# MB_Nano_V6s.net
KiCad netlist of a schematic drawn in EAGLE
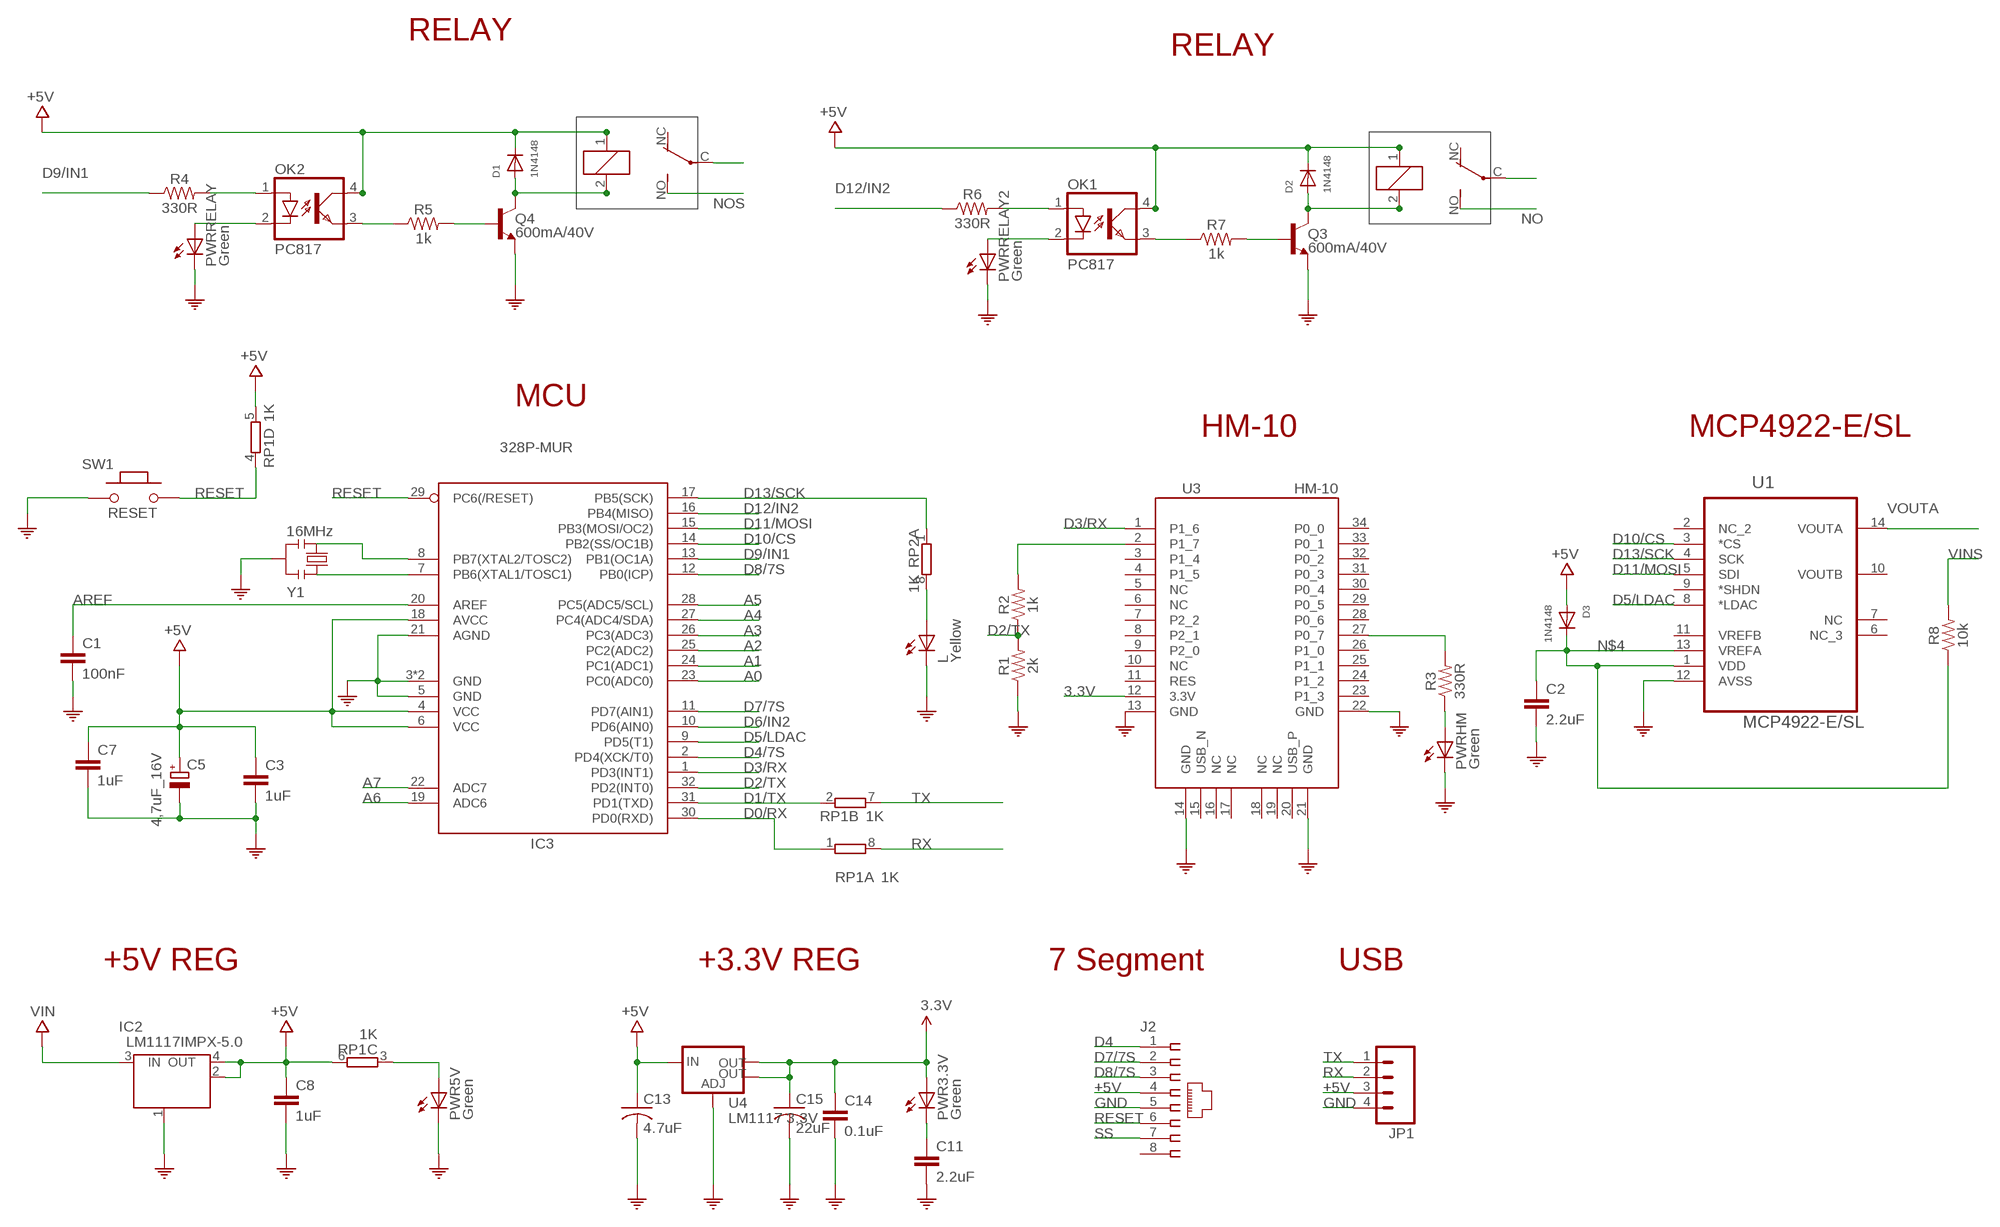
[diagram p0: schematic, sheet 1]

(export (version "E")
  (design (tool "Eeschema 10.0.6"))
  (components
    (comp (ref "C1")
      (value "100nF")
      (footprint "eagle-import:C0603-ROUND")
      (fields (field (name "PART_NUMBER") "cl10b104kbnc"))
      (libsource (lib "eagle-import") (part "0015_100NF_0603"))
    )
    (comp (ref "C2")
      (value "2.2uF")
      (footprint "eagle-import:C0603-ROUND")
      (fields (field (name "PART_NUMBER") "1uF_0603/GRM188R61E105KA12D"))
      (libsource (lib "eagle-import") (part "0006_1UF_0603/GRM188R61E105KA12D"))
    )
    (comp (ref "C3")
      (value "1uF")
      (footprint "eagle-import:C0603-ROUND")
      (fields (field (name "PART_NUMBER") "1uF_0603/GRM188R61E105KA12D"))
      (libsource (lib "eagle-import") (part "0006_1UF_0603/GRM188R61E105KA12D"))
    )
    (comp (ref "C5")
      (value "4,7uF_16V")
      (footprint "eagle-import:TAN-A")
      (fields (field (name "PART_NUMBER") "TAJA475MO16RNJ"))
      (libsource (lib "eagle-import") (part "0833_TAJA475MO16RNJ"))
    )
    (comp (ref "C7")
      (value "1uF")
      (footprint "eagle-import:C0603-ROUND")
      (fields (field (name "PART_NUMBER") "1uF_0603/GRM188R61E105KA12D"))
      (libsource (lib "eagle-import") (part "0006_1UF_0603/GRM188R61E105KA12D"))
    )
    (comp (ref "C8")
      (value "1uF")
      (footprint "eagle-import:C0603-ROUND")
      (fields (field (name "PART_NUMBER") "1uF_0603/GRM188R61E105KA12D"))
      (libsource (lib "eagle-import") (part "0006_1UF_0603/GRM188R61E105KA12D"))
    )
    (comp (ref "C11")
      (value "2.2uF")
      (footprint "eagle-import:C0603-ROUND")
      (fields (field (name "PART_NUMBER") "1uF_0603/GRM188R61E105KA12D"))
      (libsource (lib "eagle-import") (part "0006_1UF_0603/GRM188R61E105KA12D"))
    )
    (comp (ref "C13")
      (value "4.7uF")
      (footprint "eagle-import:C1206")
      (libsource (lib "eagle-import") (part "C-USC1206"))
    )
    (comp (ref "C14")
      (value "0.1uF")
      (footprint "eagle-import:0805")
      (libsource (lib "eagle-import") (part "CAP0805"))
    )
    (comp (ref "C15")
      (value "22uF")
      (footprint "eagle-import:C1206")
      (libsource (lib "eagle-import") (part "C-USC1206"))
    )
    (comp (ref "D1")
      (value "1N4148")
      (footprint "eagle-import:SOD-523")
      (libsource (lib "eagle-import") (part "DIODESOD-523"))
    )
    (comp (ref "D2")
      (value "1N4148")
      (footprint "eagle-import:SOD-523")
      (libsource (lib "eagle-import") (part "DIODESOD-523"))
    )
    (comp (ref "D3")
      (value "1N4148")
      (footprint "eagle-import:SOD-523")
      (libsource (lib "eagle-import") (part "DIODESOD-523"))
    )
    (comp (ref "IC2")
      (value "LM1117IMPX-5.0")
      (footprint "eagle-import:LINEAR_SOT223")
      (libsource (lib "eagle-import") (part "0022_LM1117IMPX-5.0"))
    )
    (comp (ref "IC3")
      (value "328P-MUR")
      (footprint "eagle-import:VQFN32")
      (fields (field (name "MANUFACTURER") "ATMEL"))
      (libsource (lib "eagle-import") (part "ATMEGA328P-32MUR"))
    )
    (comp (ref "J2")
      (value "520259-4")
      (footprint "eagle-import:520259-4")
      (libsource (lib "eagle-import") (part "520259-4"))
    )
    (comp (ref "JP1")
      (value "M04POLAR_LOCK")
      (footprint "eagle-import:MOLEX-1X4_LOCK")
      (libsource (lib "eagle-import") (part "M04POLAR_LOCK"))
    )
    (comp (ref "L")
      (value "Yellow")
      (footprint "eagle-import:CHIPLED_0805")
      (fields (field (name "PART_NUMBER") "KPT-2012YC"))
      (libsource (lib "eagle-import") (part "0044_KPT-2012YC"))
    )
    (comp (ref "OK1")
      (value "PC817")
      (footprint "eagle-import:DIL04")
      (fields (field (name "MPN") "PC817X4J000F"))
      (libsource (lib "eagle-import") (part "PC817"))
    )
    (comp (ref "OK2")
      (value "PC817")
      (footprint "eagle-import:DIL04")
      (fields (field (name "MPN") "PC817X4J000F"))
      (libsource (lib "eagle-import") (part "PC817"))
    )
    (comp (ref "PWR3.3V")
      (value "Green")
      (footprint "eagle-import:CHIPLED_0805")
      (fields (field (name "PART_NUMBER") "KPT-2012SGC"))
      (libsource (lib "eagle-import") (part "0043_KPT-2012SGC"))
    )
    (comp (ref "PWR5V")
      (value "Green")
      (footprint "eagle-import:CHIPLED_0805")
      (fields (field (name "PART_NUMBER") "KPT-2012SGC"))
      (libsource (lib "eagle-import") (part "0043_KPT-2012SGC"))
    )
    (comp (ref "PWRHM")
      (value "Green")
      (footprint "eagle-import:CHIPLED_0805")
      (fields (field (name "PART_NUMBER") "KPT-2012SGC"))
      (libsource (lib "eagle-import") (part "0043_KPT-2012SGC"))
    )
    (comp (ref "PWRRELAY")
      (value "Green")
      (footprint "eagle-import:CHIPLED_0805")
      (fields (field (name "PART_NUMBER") "KPT-2012SGC"))
      (libsource (lib "eagle-import") (part "0043_KPT-2012SGC"))
    )
    (comp (ref "PWRRELAY2")
      (value "Green")
      (footprint "eagle-import:CHIPLED_0805")
      (fields (field (name "PART_NUMBER") "KPT-2012SGC"))
      (libsource (lib "eagle-import") (part "0043_KPT-2012SGC"))
    )
    (comp (ref "Q3")
      (value "600mA/40V")
      (footprint "eagle-import:SOT23-3")
      (libsource (lib "eagle-import") (part "TRANS_NPN-MMBT2222AL"))
    )
    (comp (ref "Q4")
      (value "600mA/40V")
      (footprint "eagle-import:SOT23-3")
      (libsource (lib "eagle-import") (part "TRANS_NPN-MMBT2222AL"))
    )
    (comp (ref "R1")
      (value "2k")
      (footprint "eagle-import:0603")
      (libsource (lib "eagle-import") (part "33OHM-0603-1/10W-1%"))
    )
    (comp (ref "R2")
      (value "1k")
      (footprint "eagle-import:0603")
      (libsource (lib "eagle-import") (part "33OHM-0603-1/10W-1%"))
    )
    (comp (ref "R3")
      (value "330R")
      (footprint "eagle-import:0603")
      (libsource (lib "eagle-import") (part "33OHM-0603-1/10W-1%"))
    )
    (comp (ref "R4")
      (value "330R")
      (footprint "eagle-import:0603")
      (libsource (lib "eagle-import") (part "33OHM-0603-1/10W-1%"))
    )
    (comp (ref "R5")
      (value "1k")
      (footprint "eagle-import:0603")
      (libsource (lib "eagle-import") (part "1KOHM-0603-1/10W-1%"))
    )
    (comp (ref "R6")
      (value "330R")
      (footprint "eagle-import:0603")
      (libsource (lib "eagle-import") (part "33OHM-0603-1/10W-1%"))
    )
    (comp (ref "R7")
      (value "1k")
      (footprint "eagle-import:0603")
      (libsource (lib "eagle-import") (part "1KOHM-0603-1/10W-1%"))
    )
    (comp (ref "R8")
      (value "10k")
      (footprint "eagle-import:0603")
      (libsource (lib "eagle-import") (part "1KOHM-0603-1/10W-1%"))
    )
    (comp (ref "RELAY5VDC")
      (value "RELAY 5VDC")
      (footprint "eagle-import:CQ1")
      (libsource (lib "eagle-import") (part "CQ1-12V"))
    )
    (comp (ref "RELAY5VDC1")
      (value "RELAY 5VDC")
      (footprint "eagle-import:CQ1")
      (libsource (lib "eagle-import") (part "CQ1-12V"))
    )
    (comp (ref "RP1")
      (value "1K")
      (footprint "eagle-import:CAY16")
      (fields (field (name "PART_NUMBER") "064R_1K_/_CAY16-102J4LF"))
      (libsource (lib "eagle-import") (part "0005_064R_1K_/_CAY16-102J4LF"))
    )
    (comp (ref "RP2")
      (value "1K")
      (footprint "eagle-import:CAY16")
      (fields (field (name "PART_NUMBER") "064R_1K_/_CAY16-102J4LF"))
      (libsource (lib "eagle-import") (part "0005_064R_1K_/_CAY16-102J4LF"))
    )
    (comp (ref "SW1")
      (value "RESET")
      (footprint "eagle-import:SMD_157SW")
      (fields (field (name "PART_NUMBER") "IT-1185AP1C-160G-G_T&R"))
      (libsource (lib "eagle-import") (part "0173_IT-1185AP1C-160G-G_T&R"))
    )
    (comp (ref "U1")
      (value "MCP4922-E/SL")
      (footprint "eagle-import:SOIC127P600X175-14N")
      (libsource (lib "eagle-import") (part "MCP4922-E/SL"))
    )
    (comp (ref "U3")
      (value "HM-10")
      (footprint "eagle-import:HM-10")
      (libsource (lib "eagle-import") (part "HM-10"))
    )
    (comp (ref "U4")
      (value "LM1117 3.3V")
      (footprint "eagle-import:SOT223")
      (libsource (lib "eagle-import") (part "V_REG_LM1117SOT223"))
    )
    (comp (ref "Y1")
      (value "16MHz")
      (footprint "eagle-import:RESONATOR")
      (fields (field (name "PART_NUMBER") "CSTCE16M0V53-R0"))
      (libsource (lib "eagle-import") (part "0011_CSTCE16M0V53-R0"))
    )
  )
  (nets
    (net (code "1") (name "+5V") (class "Default")
      (node (ref "C13") (pin "1") (pinfunction "1_1") (pintype "passive"))
      (node (ref "C3") (pin "1") (pinfunction "1_1") (pintype "passive"))
      (node (ref "C5") (pin "1") (pinfunction "+_1") (pintype "passive"))
      (node (ref "C7") (pin "1") (pinfunction "1_1") (pintype "passive"))
      (node (ref "C8") (pin "1") (pinfunction "1_1") (pintype "passive"))
      (node (ref "D1") (pin "K") (pinfunction "C_K") (pintype "passive"))
      (node (ref "D2") (pin "K") (pinfunction "C_K") (pintype "passive"))
      (node (ref "D3") (pin "A") (pinfunction "A_A") (pintype "passive"))
      (node (ref "IC2") (pin "2") (pinfunction "OUT_2") (pintype "passive"))
      (node (ref "IC2") (pin "4") (pinfunction "OUT_4") (pintype "passive"))
      (node (ref "IC3") (pin "18") (pinfunction "AVCC_18") (pintype "bidirectional"))
      (node (ref "IC3") (pin "4") (pinfunction "VCC_4") (pintype "bidirectional"))
      (node (ref "IC3") (pin "6") (pinfunction "VCC_6") (pintype "bidirectional"))
      (node (ref "J2") (pin "4") (pinfunction "4_4") (pintype "passive"))
      (node (ref "JP1") (pin "3") (pinfunction "3_3") (pintype "passive"))
      (node (ref "OK1") (pin "4") (pinfunction "COL_4") (pintype "passive"))
      (node (ref "OK2") (pin "4") (pinfunction "COL_4") (pintype "passive"))
      (node (ref "RELAY5VDC") (pin "1") (pinfunction "1_1") (pintype "passive"))
      (node (ref "RELAY5VDC1") (pin "1") (pinfunction "1_1") (pintype "passive"))
      (node (ref "RP1") (pin "5") (pinfunction "2_5") (pintype "passive"))
      (node (ref "RP1") (pin "6") (pinfunction "2_6") (pintype "passive"))
      (node (ref "U4") (pin "3") (pinfunction "IN_3") (pintype "input"))
    )
    (net (code "2") (name "/A0") (class "Default")
      (node (ref "IC3") (pin "23") (pinfunction "PC0(ADC0)_23") (pintype "bidirectional"))
    )
    (net (code "3") (name "/A1") (class "Default")
      (node (ref "IC3") (pin "24") (pinfunction "PC1(ADC1)_24") (pintype "bidirectional"))
    )
    (net (code "4") (name "/A2") (class "Default")
      (node (ref "IC3") (pin "25") (pinfunction "PC2(ADC2)_25") (pintype "bidirectional"))
    )
    (net (code "5") (name "/A3") (class "Default")
      (node (ref "IC3") (pin "26") (pinfunction "PC3(ADC3)_26") (pintype "bidirectional"))
    )
    (net (code "6") (name "/A4") (class "Default")
      (node (ref "IC3") (pin "27") (pinfunction "PC4(ADC4/SDA)_27") (pintype "bidirectional"))
    )
    (net (code "7") (name "/A5") (class "Default")
      (node (ref "IC3") (pin "28") (pinfunction "PC5(ADC5/SCL)_28") (pintype "bidirectional"))
    )
    (net (code "8") (name "/A6") (class "Default")
      (node (ref "IC3") (pin "19") (pinfunction "ADC6_19") (pintype "bidirectional"))
    )
    (net (code "9") (name "/A7") (class "Default")
      (node (ref "IC3") (pin "22") (pinfunction "ADC7_22") (pintype "bidirectional"))
    )
    (net (code "10") (name "/AREF") (class "Default")
      (node (ref "C1") (pin "1") (pinfunction "1_1") (pintype "passive"))
      (node (ref "IC3") (pin "20") (pinfunction "AREF_20") (pintype "bidirectional"))
    )
    (net (code "11") (name "/D0{slash}RX") (class "Default")
      (node (ref "IC3") (pin "30") (pinfunction "PD0(RXD)_30") (pintype "bidirectional"))
      (node (ref "RP1") (pin "1") (pinfunction "1_1") (pintype "passive"))
    )
    (net (code "12") (name "/D1{slash}TX") (class "Default")
      (node (ref "IC3") (pin "31") (pinfunction "PD1(TXD)_31") (pintype "bidirectional"))
      (node (ref "RP1") (pin "2") (pinfunction "1_2") (pintype "passive"))
    )
    (net (code "13") (name "/D2{slash}TX") (class "Default")
      (node (ref "IC3") (pin "32") (pinfunction "PD2(INT0)_32") (pintype "bidirectional"))
      (node (ref "R1") (pin "2") (pinfunction "2_2") (pintype "passive"))
      (node (ref "R2") (pin "1") (pinfunction "1_1") (pintype "passive"))
    )
    (net (code "14") (name "/D3{slash}RX") (class "Default")
      (node (ref "IC3") (pin "1") (pinfunction "PD3(INT1)_1") (pintype "bidirectional"))
      (node (ref "U3") (pin "1") (pinfunction "P1_6_1") (pintype "bidirectional"))
    )
    (net (code "15") (name "/D4") (class "Default")
      (node (ref "J2") (pin "1") (pinfunction "1_1") (pintype "passive"))
    )
    (net (code "16") (name "/D4{slash}7S") (class "Default")
      (node (ref "IC3") (pin "2") (pinfunction "PD4(XCK/T0)_2") (pintype "bidirectional"))
    )
    (net (code "17") (name "/D5{slash}LDAC") (class "Default")
      (node (ref "IC3") (pin "9") (pinfunction "PD5(T1)_9") (pintype "bidirectional"))
      (node (ref "U1") (pin "8") (pinfunction "*LDAC_8") (pintype "input"))
    )
    (net (code "18") (name "/D6{slash}IN2") (class "Default")
      (node (ref "IC3") (pin "10") (pinfunction "PD6(AIN0)_10") (pintype "bidirectional"))
    )
    (net (code "19") (name "/D7{slash}7S") (class "Default")
      (node (ref "IC3") (pin "11") (pinfunction "PD7(AIN1)_11") (pintype "bidirectional"))
      (node (ref "J2") (pin "2") (pinfunction "2_2") (pintype "passive"))
    )
    (net (code "20") (name "/D8{slash}7S") (class "Default")
      (node (ref "IC3") (pin "12") (pinfunction "PB0(ICP)_12") (pintype "bidirectional"))
      (node (ref "J2") (pin "3") (pinfunction "3_3") (pintype "passive"))
    )
    (net (code "21") (name "/D9{slash}IN1") (class "Default")
      (node (ref "IC3") (pin "13") (pinfunction "PB1(OC1A)_13") (pintype "bidirectional"))
      (node (ref "R4") (pin "1") (pinfunction "1_1") (pintype "passive"))
    )
    (net (code "22") (name "/D10{slash}CS") (class "Default")
      (node (ref "IC3") (pin "14") (pinfunction "PB2(SS/OC1B)_14") (pintype "bidirectional"))
      (node (ref "U1") (pin "3") (pinfunction "*CS_3") (pintype "input"))
    )
    (net (code "23") (name "/D11{slash}MOSI") (class "Default")
      (node (ref "IC3") (pin "15") (pinfunction "PB3(MOSI/OC2)_15") (pintype "bidirectional"))
      (node (ref "U1") (pin "5") (pinfunction "SDI_5") (pintype "input"))
    )
    (net (code "24") (name "/D12{slash}IN2") (class "Default")
      (node (ref "IC3") (pin "16") (pinfunction "PB4(MISO)_16") (pintype "bidirectional"))
      (node (ref "R6") (pin "1") (pinfunction "1_1") (pintype "passive"))
    )
    (net (code "25") (name "/D13{slash}SCK") (class "Default")
      (node (ref "IC3") (pin "17") (pinfunction "PB5(SCK)_17") (pintype "bidirectional"))
      (node (ref "RP2") (pin "1") (pinfunction "1_1") (pintype "passive"))
      (node (ref "U1") (pin "4") (pinfunction "SCK_4") (pintype "input"))
    )
    (net (code "26") (name "/GND") (class "Default")
      (node (ref "J2") (pin "5") (pinfunction "5_5") (pintype "passive"))
      (node (ref "JP1") (pin "4") (pinfunction "4_4") (pintype "passive"))
    )
    (net (code "27") (name "/N$4") (class "Default")
      (node (ref "C11") (pin "1") (pinfunction "1_1") (pintype "passive"))
      (node (ref "C2") (pin "1") (pinfunction "1_1") (pintype "passive"))
      (node (ref "D3") (pin "K") (pinfunction "C_K") (pintype "passive"))
      (node (ref "PWR3.3V") (pin "C") (pinfunction "C_C") (pintype "passive"))
      (node (ref "R8") (pin "1") (pinfunction "1_1") (pintype "passive"))
      (node (ref "U1") (pin "1") (pinfunction "VDD_1") (pintype "power_in"))
      (node (ref "U1") (pin "13") (pinfunction "VREFA_13") (pintype "input"))
    )
    (net (code "28") (name "/NO") (class "Default")
      (node (ref "RELAY5VDC") (pin "NO") (pinfunction "S_NO") (pintype "passive"))
    )
    (net (code "29") (name "/NOS") (class "Default")
      (node (ref "RELAY5VDC1") (pin "NO") (pinfunction "S_NO") (pintype "passive"))
    )
    (net (code "30") (name "/RESET") (class "Default")
      (node (ref "IC3") (pin "29") (pinfunction "PC6(/RESET)_29") (pintype "bidirectional"))
      (node (ref "J2") (pin "6") (pinfunction "6_6") (pintype "passive"))
      (node (ref "RP1") (pin "4") (pinfunction "1_4") (pintype "passive"))
      (node (ref "SW1") (pin "2") (pinfunction "2_2") (pintype "passive"))
    )
    (net (code "31") (name "/RX") (class "Default")
      (node (ref "JP1") (pin "2") (pinfunction "2_2") (pintype "passive"))
      (node (ref "RP1") (pin "8") (pinfunction "2_8") (pintype "passive"))
    )
    (net (code "32") (name "/SS") (class "Default")
      (node (ref "J2") (pin "7") (pinfunction "7_7") (pintype "passive"))
    )
    (net (code "33") (name "/TX") (class "Default")
      (node (ref "JP1") (pin "1") (pinfunction "1_1") (pintype "passive"))
      (node (ref "RP1") (pin "7") (pinfunction "2_7") (pintype "passive"))
    )
    (net (code "34") (name "/VINS") (class "Default")
      (node (ref "R8") (pin "2") (pinfunction "2_2") (pintype "passive"))
    )
    (net (code "35") (name "/VOUTA") (class "Default")
      (node (ref "U1") (pin "14") (pinfunction "VOUTA_14") (pintype "output"))
    )
    (net (code "36") (name "3.3V") (class "Default")
      (node (ref "C14") (pin "1") (pinfunction "1_1") (pintype "passive"))
      (node (ref "C15") (pin "1") (pinfunction "1_1") (pintype "passive"))
      (node (ref "PWR3.3V") (pin "A") (pinfunction "A_A") (pintype "passive"))
      (node (ref "U3") (pin "12") (pinfunction "3.3V_12") (pintype "bidirectional"))
      (node (ref "U4") (pin "2") (pinfunction "OUT_2") (pintype "output"))
      (node (ref "U4") (pin "4") (pinfunction "OUT_4") (pintype "output"))
    )
    (net (code "37") (name "COM") (class "Default")
      (node (ref "C1") (pin "2") (pinfunction "2_2") (pintype "passive"))
      (node (ref "C11") (pin "2") (pinfunction "2_2") (pintype "passive"))
      (node (ref "C13") (pin "2") (pinfunction "2_2") (pintype "passive"))
      (node (ref "C14") (pin "2") (pinfunction "2_2") (pintype "passive"))
      (node (ref "C15") (pin "2") (pinfunction "2_2") (pintype "passive"))
      (node (ref "C2") (pin "2") (pinfunction "2_2") (pintype "passive"))
      (node (ref "C3") (pin "2") (pinfunction "2_2") (pintype "passive"))
      (node (ref "C5") (pin "2") (pinfunction "-_2") (pintype "passive"))
      (node (ref "C7") (pin "2") (pinfunction "2_2") (pintype "passive"))
      (node (ref "C8") (pin "2") (pinfunction "2_2") (pintype "passive"))
      (node (ref "IC2") (pin "1") (pinfunction "GND/ADJ_1") (pintype "input"))
      (node (ref "IC3") (pin "21") (pinfunction "AGND_21") (pintype "bidirectional"))
      (node (ref "IC3") (pin "3") (pinfunction "GND_3") (pintype "bidirectional"))
      (node (ref "IC3") (pin "33") (pinfunction "GND_33") (pintype "bidirectional"))
      (node (ref "IC3") (pin "5") (pinfunction "GND_5") (pintype "bidirectional"))
      (node (ref "L") (pin "C") (pinfunction "C_C") (pintype "passive"))
      (node (ref "PWR5V") (pin "C") (pinfunction "C_C") (pintype "passive"))
      (node (ref "PWRHM") (pin "C") (pinfunction "C_C") (pintype "passive"))
      (node (ref "PWRRELAY") (pin "C") (pinfunction "C_C") (pintype "passive"))
      (node (ref "PWRRELAY2") (pin "C") (pinfunction "C_C") (pintype "passive"))
      (node (ref "Q3") (pin "2") (pinfunction "E_2") (pintype "passive"))
      (node (ref "Q4") (pin "2") (pinfunction "E_2") (pintype "passive"))
      (node (ref "R1") (pin "1") (pinfunction "1_1") (pintype "passive"))
      (node (ref "SW1") (pin "1") (pinfunction "1_1") (pintype "passive"))
      (node (ref "U1") (pin "12") (pinfunction "AVSS_12") (pintype "passive"))
      (node (ref "U3") (pin "13") (pinfunction "GND_13") (pintype "bidirectional"))
      (node (ref "U3") (pin "14") (pinfunction "GND_14") (pintype "bidirectional"))
      (node (ref "U3") (pin "21") (pinfunction "GND_21") (pintype "bidirectional"))
      (node (ref "U3") (pin "22") (pinfunction "GND_22") (pintype "bidirectional"))
      (node (ref "U4") (pin "1") (pinfunction "ADJ_1") (pintype "input"))
      (node (ref "Y1") (pin "2") (pinfunction "2_2") (pintype "passive"))
    )
    (net (code "38") (name "Net-(IC3-PB6(XTAL1{slash}TOSC1))") (class "Default")
      (node (ref "IC3") (pin "7") (pinfunction "PB6(XTAL1/TOSC1)_7") (pintype "bidirectional"))
      (node (ref "Y1") (pin "1") (pinfunction "1_1") (pintype "passive"))
    )
    (net (code "39") (name "Net-(IC3-PB7(XTAL2{slash}TOSC2))") (class "Default")
      (node (ref "IC3") (pin "8") (pinfunction "PB7(XTAL2/TOSC2)_8") (pintype "bidirectional"))
      (node (ref "Y1") (pin "3") (pinfunction "3_3") (pintype "passive"))
    )
    (net (code "40") (name "Net-(OK1-A)") (class "Default")
      (node (ref "OK1") (pin "1") (pinfunction "A_1") (pintype "passive"))
      (node (ref "R6") (pin "2") (pinfunction "2_2") (pintype "passive"))
    )
    (net (code "41") (name "Net-(OK1-C)") (class "Default")
      (node (ref "OK1") (pin "2") (pinfunction "C_2") (pintype "passive"))
      (node (ref "PWRRELAY2") (pin "A") (pinfunction "A_A") (pintype "passive"))
    )
    (net (code "42") (name "Net-(OK1-EMIT)") (class "Default")
      (node (ref "OK1") (pin "3") (pinfunction "EMIT_3") (pintype "passive"))
      (node (ref "R7") (pin "1") (pinfunction "1_1") (pintype "passive"))
    )
    (net (code "43") (name "Net-(OK2-A)") (class "Default")
      (node (ref "OK2") (pin "1") (pinfunction "A_1") (pintype "passive"))
      (node (ref "R4") (pin "2") (pinfunction "2_2") (pintype "passive"))
    )
    (net (code "44") (name "Net-(OK2-C)") (class "Default")
      (node (ref "OK2") (pin "2") (pinfunction "C_2") (pintype "passive"))
      (node (ref "PWRRELAY") (pin "A") (pinfunction "A_A") (pintype "passive"))
    )
    (net (code "45") (name "Net-(OK2-EMIT)") (class "Default")
      (node (ref "OK2") (pin "3") (pinfunction "EMIT_3") (pintype "passive"))
      (node (ref "R5") (pin "1") (pinfunction "1_1") (pintype "passive"))
    )
    (net (code "46") (name "Net-(PWRHM-PadA)") (class "Default")
      (node (ref "PWRHM") (pin "A") (pinfunction "A_A") (pintype "passive"))
      (node (ref "R3") (pin "1") (pinfunction "1_1") (pintype "passive"))
    )
    (net (code "47") (name "Net-(Q3-B)") (class "Default")
      (node (ref "Q3") (pin "1") (pinfunction "B_1") (pintype "passive"))
      (node (ref "R7") (pin "2") (pinfunction "2_2") (pintype "passive"))
    )
    (net (code "48") (name "Net-(Q3-C)") (class "Default")
      (node (ref "D2") (pin "A") (pinfunction "A_A") (pintype "passive"))
      (node (ref "Q3") (pin "3") (pinfunction "C_3") (pintype "passive"))
      (node (ref "RELAY5VDC") (pin "2") (pinfunction "2_2") (pintype "passive"))
    )
    (net (code "49") (name "Net-(Q4-B)") (class "Default")
      (node (ref "Q4") (pin "1") (pinfunction "B_1") (pintype "passive"))
      (node (ref "R5") (pin "2") (pinfunction "2_2") (pintype "passive"))
    )
    (net (code "50") (name "Net-(Q4-C)") (class "Default")
      (node (ref "D1") (pin "A") (pinfunction "A_A") (pintype "passive"))
      (node (ref "Q4") (pin "3") (pinfunction "C_3") (pintype "passive"))
      (node (ref "RELAY5VDC1") (pin "2") (pinfunction "2_2") (pintype "passive"))
    )
    (net (code "51") (name "Net-(RP1C-1)") (class "Default")
      (node (ref "PWR5V") (pin "A") (pinfunction "A_A") (pintype "passive"))
      (node (ref "RP1") (pin "3") (pinfunction "1_3") (pintype "passive"))
    )
    (net (code "52") (name "Net-(RP2A-2)") (class "Default")
      (node (ref "L") (pin "A") (pinfunction "A_A") (pintype "passive"))
      (node (ref "RP2") (pin "8") (pinfunction "2_8") (pintype "passive"))
    )
    (net (code "53") (name "Net-(U3-P0_7)") (class "Default")
      (node (ref "R3") (pin "2") (pinfunction "2_2") (pintype "passive"))
      (node (ref "U3") (pin "27") (pinfunction "P0_7_27") (pintype "bidirectional"))
    )
    (net (code "54") (name "Net-(U3-P1_7)") (class "Default")
      (node (ref "R2") (pin "2") (pinfunction "2_2") (pintype "passive"))
      (node (ref "U3") (pin "2") (pinfunction "P1_7_2") (pintype "bidirectional"))
    )
    (net (code "55") (name "VIN") (class "Default")
      (node (ref "IC2") (pin "3") (pinfunction "IN_3") (pintype "input"))
    )
    (net (code "56") (name "unconnected-(J2-Pad8)") (class "Default")
      (node (ref "J2") (pin "8") (pinfunction "8_8") (pintype "passive"))
    )
    (net (code "57") (name "unconnected-(RELAY5VDC1B-O-PadNC)") (class "Default")
      (node (ref "RELAY5VDC1") (pin "NC") (pinfunction "O_NC") (pintype "passive"))
    )
    (net (code "58") (name "unconnected-(RELAY5VDC1B-P-PadC)") (class "Default")
      (node (ref "RELAY5VDC1") (pin "C") (pinfunction "P_C") (pintype "passive"))
    )
    (net (code "59") (name "unconnected-(RELAY5VDCB-O-PadNC)") (class "Default")
      (node (ref "RELAY5VDC") (pin "NC") (pinfunction "O_NC") (pintype "passive"))
    )
    (net (code "60") (name "unconnected-(RELAY5VDCB-P-PadC)") (class "Default")
      (node (ref "RELAY5VDC") (pin "C") (pinfunction "P_C") (pintype "passive"))
    )
    (net (code "61") (name "unconnected-(U1-*SHDN-Pad9)") (class "Default")
      (node (ref "U1") (pin "9") (pinfunction "*SHDN_9") (pintype "input"))
    )
    (net (code "62") (name "unconnected-(U1-NC-Pad7)") (class "Default")
      (node (ref "U1") (pin "7") (pinfunction "NC_7") (pintype "no_connect"))
    )
    (net (code "63") (name "unconnected-(U1-NC_2-Pad2)") (class "Default")
      (node (ref "U1") (pin "2") (pinfunction "NC_2_2") (pintype "no_connect"))
    )
    (net (code "64") (name "unconnected-(U1-NC_3-Pad6)") (class "Default")
      (node (ref "U1") (pin "6") (pinfunction "NC_3_6") (pintype "no_connect"))
    )
    (net (code "65") (name "unconnected-(U1-VOUTB-Pad10)") (class "Default")
      (node (ref "U1") (pin "10") (pinfunction "VOUTB_10") (pintype "output"))
    )
    (net (code "66") (name "unconnected-(U1-VREFB-Pad11)") (class "Default")
      (node (ref "U1") (pin "11") (pinfunction "VREFB_11") (pintype "input"))
    )
    (net (code "67") (name "unconnected-(U3-NC-Pad5)") (class "Default")
      (node (ref "U3") (pin "5") (pinfunction "NC_5") (pintype "bidirectional"))
    )
    (net (code "68") (name "unconnected-(U3-NC-Pad6)") (class "Default")
      (node (ref "U3") (pin "6") (pinfunction "NC_6") (pintype "bidirectional"))
    )
    (net (code "69") (name "unconnected-(U3-NC-Pad10)") (class "Default")
      (node (ref "U3") (pin "10") (pinfunction "NC_10") (pintype "bidirectional"))
    )
    (net (code "70") (name "unconnected-(U3-NC-Pad16)") (class "Default")
      (node (ref "U3") (pin "16") (pinfunction "NC_16") (pintype "bidirectional"))
    )
    (net (code "71") (name "unconnected-(U3-NC-Pad17)") (class "Default")
      (node (ref "U3") (pin "17") (pinfunction "NC_17") (pintype "bidirectional"))
    )
    (net (code "72") (name "unconnected-(U3-NC-Pad18)") (class "Default")
      (node (ref "U3") (pin "18") (pinfunction "NC_18") (pintype "bidirectional"))
    )
    (net (code "73") (name "unconnected-(U3-NC-Pad19)") (class "Default")
      (node (ref "U3") (pin "19") (pinfunction "NC_19") (pintype "bidirectional"))
    )
    (net (code "74") (name "unconnected-(U3-P0_0-Pad34)") (class "Default")
      (node (ref "U3") (pin "34") (pinfunction "P0_0_34") (pintype "bidirectional"))
    )
    (net (code "75") (name "unconnected-(U3-P0_1-Pad33)") (class "Default")
      (node (ref "U3") (pin "33") (pinfunction "P0_1_33") (pintype "bidirectional"))
    )
    (net (code "76") (name "unconnected-(U3-P0_2-Pad32)") (class "Default")
      (node (ref "U3") (pin "32") (pinfunction "P0_2_32") (pintype "bidirectional"))
    )
    (net (code "77") (name "unconnected-(U3-P0_3-Pad31)") (class "Default")
      (node (ref "U3") (pin "31") (pinfunction "P0_3_31") (pintype "bidirectional"))
    )
    (net (code "78") (name "unconnected-(U3-P0_4-Pad30)") (class "Default")
      (node (ref "U3") (pin "30") (pinfunction "P0_4_30") (pintype "bidirectional"))
    )
    (net (code "79") (name "unconnected-(U3-P0_5-Pad29)") (class "Default")
      (node (ref "U3") (pin "29") (pinfunction "P0_5_29") (pintype "bidirectional"))
    )
    (net (code "80") (name "unconnected-(U3-P0_6-Pad28)") (class "Default")
      (node (ref "U3") (pin "28") (pinfunction "P0_6_28") (pintype "bidirectional"))
    )
    (net (code "81") (name "unconnected-(U3-P1_0-Pad26)") (class "Default")
      (node (ref "U3") (pin "26") (pinfunction "P1_0_26") (pintype "bidirectional"))
    )
    (net (code "82") (name "unconnected-(U3-P1_1-Pad25)") (class "Default")
      (node (ref "U3") (pin "25") (pinfunction "P1_1_25") (pintype "bidirectional"))
    )
    (net (code "83") (name "unconnected-(U3-P1_2-Pad24)") (class "Default")
      (node (ref "U3") (pin "24") (pinfunction "P1_2_24") (pintype "bidirectional"))
    )
    (net (code "84") (name "unconnected-(U3-P1_3-Pad23)") (class "Default")
      (node (ref "U3") (pin "23") (pinfunction "P1_3_23") (pintype "bidirectional"))
    )
    (net (code "85") (name "unconnected-(U3-P1_4-Pad3)") (class "Default")
      (node (ref "U3") (pin "3") (pinfunction "P1_4_3") (pintype "bidirectional"))
    )
    (net (code "86") (name "unconnected-(U3-P1_5-Pad4)") (class "Default")
      (node (ref "U3") (pin "4") (pinfunction "P1_5_4") (pintype "bidirectional"))
    )
    (net (code "87") (name "unconnected-(U3-P2_0-Pad9)") (class "Default")
      (node (ref "U3") (pin "9") (pinfunction "P2_0_9") (pintype "bidirectional"))
    )
    (net (code "88") (name "unconnected-(U3-P2_1-Pad8)") (class "Default")
      (node (ref "U3") (pin "8") (pinfunction "P2_1_8") (pintype "bidirectional"))
    )
    (net (code "89") (name "unconnected-(U3-P2_2-Pad7)") (class "Default")
      (node (ref "U3") (pin "7") (pinfunction "P2_2_7") (pintype "bidirectional"))
    )
    (net (code "90") (name "unconnected-(U3-RES-Pad11)") (class "Default")
      (node (ref "U3") (pin "11") (pinfunction "RES_11") (pintype "bidirectional"))
    )
    (net (code "91") (name "unconnected-(U3-USB_N-Pad15)") (class "Default")
      (node (ref "U3") (pin "15") (pinfunction "USB_N_15") (pintype "bidirectional"))
    )
    (net (code "92") (name "unconnected-(U3-USB_P-Pad20)") (class "Default")
      (node (ref "U3") (pin "20") (pinfunction "USB_P_20") (pintype "bidirectional"))
    )
  )
)
